# ST_LINK_V2-1.net
KiCad netlist of a schematic drawn in Altium Designer
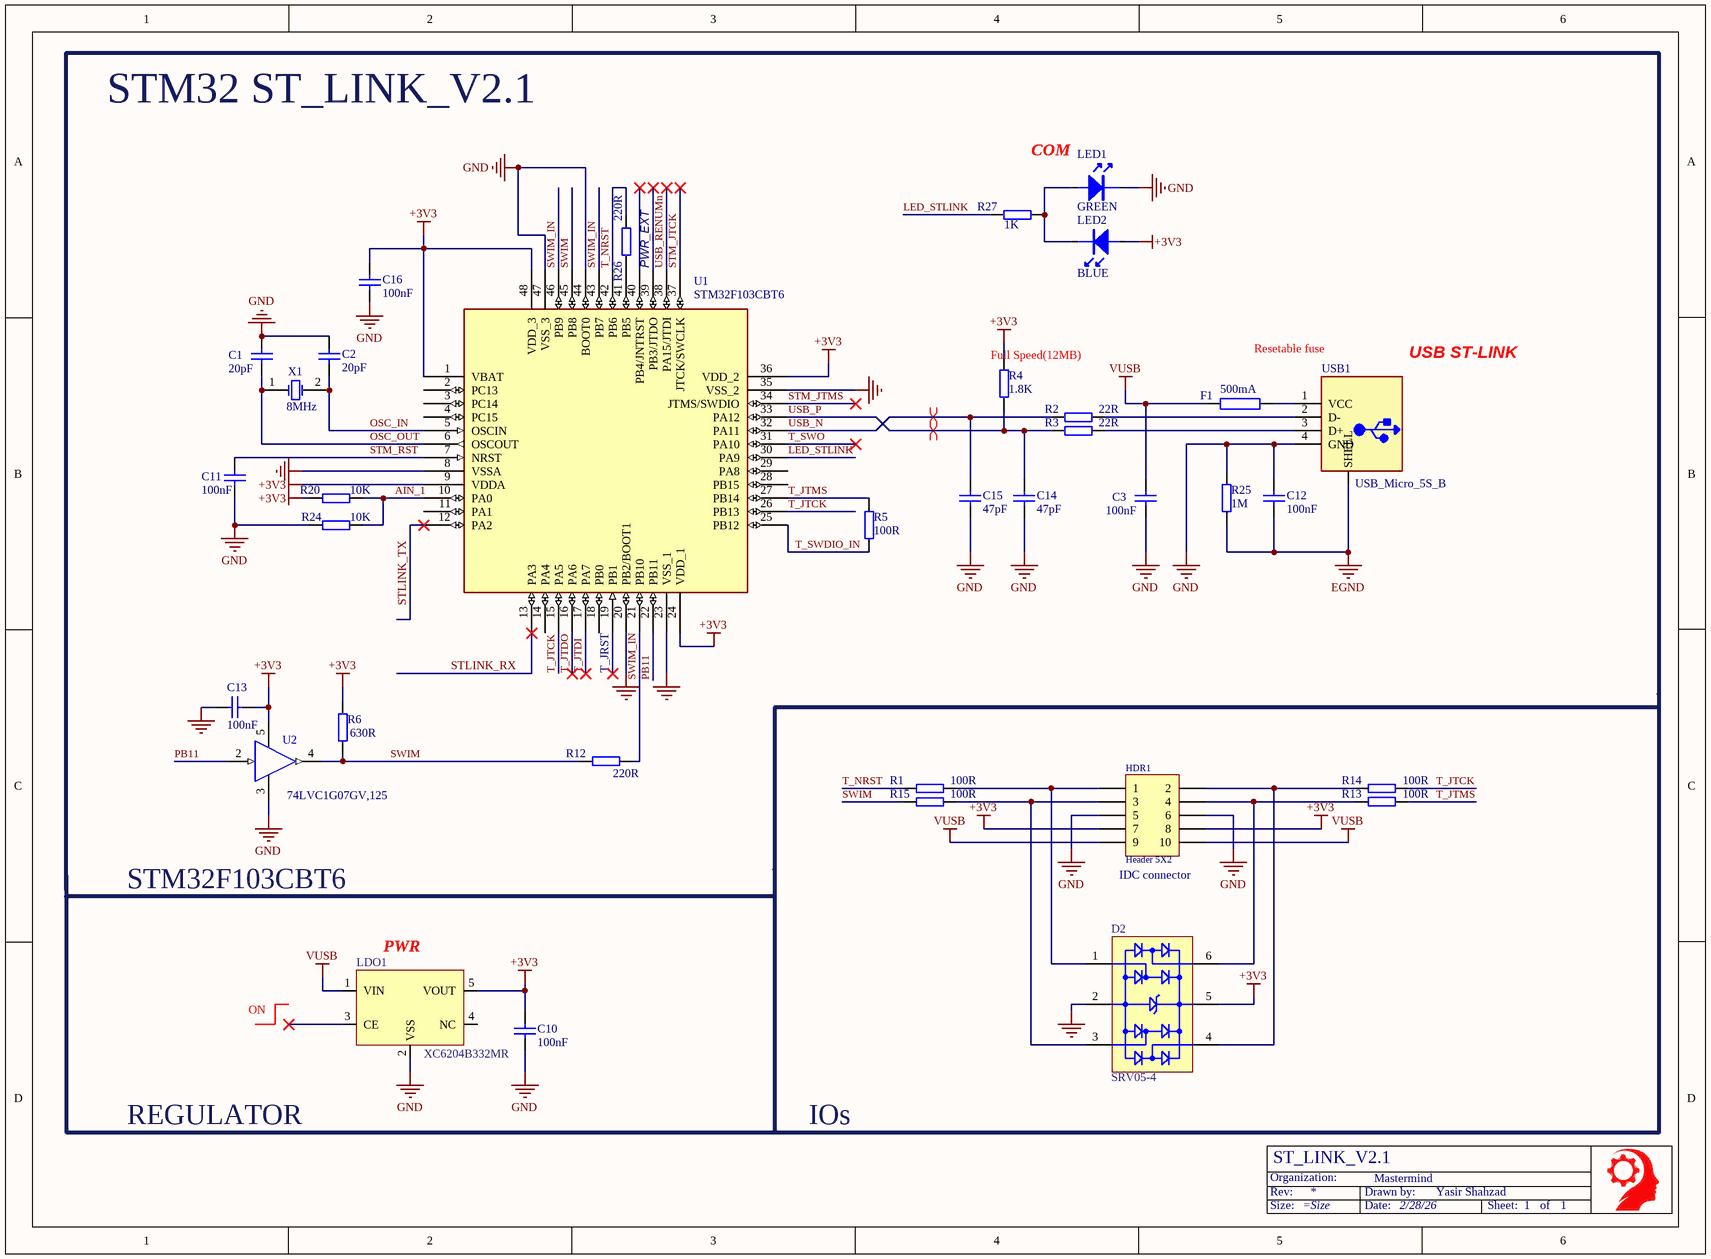
[diagram p0: ST_LINK_V2-1.SchDoc]

(export (version "E")
  (design (tool "Eeschema 10.0.6"))
  (components
    (comp (ref "*")
      (value "TitleBlock")
      (description "Title Block for Schematic Sheets")
      (libsource (lib "Mastermind Devices") (part "TitleBlock"))
    )
    (comp (ref "C1")
      (value "20pF")
      (footprint "C0603-NO")
      (description "CAP CER ?nF ?V X7R 0603")
      (libsource (lib "Mastermind Devices") (part "Cap_0603"))
    )
    (comp (ref "C2")
      (value "20pF")
      (footprint "C0603-NO")
      (description "CAP CER ?nF ?V X7R 0603")
      (libsource (lib "Mastermind Devices") (part "Cap_0603"))
    )
    (comp (ref "C3")
      (value "100nF")
      (footprint "C0603-NO")
      (description "CAP CER ?nF ?V X7R 0603")
      (libsource (lib "Mastermind Devices") (part "Cap_0603"))
    )
    (comp (ref "C10")
      (value "100nF")
      (footprint "C0603-NO")
      (description "CAP CER ?nF ?V X7R 0603")
      (libsource (lib "Mastermind Devices") (part "Cap_0603"))
    )
    (comp (ref "C11")
      (value "100nF")
      (footprint "C0603-NO")
      (description "CAP CER ?nF ?V X7R 0603")
      (libsource (lib "Mastermind Devices") (part "Cap_0603"))
    )
    (comp (ref "C12")
      (value "100nF")
      (footprint "C0603-NO")
      (description "CAP CER ?nF ?V X7R 0603")
      (libsource (lib "Mastermind Devices") (part "Cap_0603"))
    )
    (comp (ref "C13")
      (value "100nF")
      (footprint "C0603-NO")
      (description "CAP CER ?nF ?V X7R 0603")
      (libsource (lib "Mastermind Devices") (part "Cap_0603"))
    )
    (comp (ref "C14")
      (value "47pF")
      (footprint "C0603-NO")
      (description "CAP CER ?nF ?V X7R 0603")
      (libsource (lib "Mastermind Devices") (part "Cap_0603"))
    )
    (comp (ref "C15")
      (value "47pF")
      (footprint "C0603-NO")
      (description "CAP CER ?nF ?V X7R 0603")
      (libsource (lib "Mastermind Devices") (part "Cap_0603"))
    )
    (comp (ref "C16")
      (value "100nF")
      (footprint "C0603-NO")
      (description "CAP CER ?nF ?V X7R 0603")
      (libsource (lib "Mastermind Devices") (part "Cap_0603"))
    )
    (comp (ref "D2")
      (value "SRV05-4")
      (footprint "SOT23-6")
      (fields (field (name "MANUFACTURER") "MSKSEMI(美森科)"))
      (libsource (lib "ST_LINK_V2-1") (part "SRV05-4"))
    )
    (comp (ref "F1")
      (value "500mA")
      (footprint "F1206")
      (description "Resetable fuse")
      (fields (field (name "Comment") "Resistor_FUSE"))
      (libsource (lib "adafruit") (part "Resistor_FUSE"))
    )
    (comp (ref "HDR1")
      (value "Header 5X2")
      (footprint "IDC10_2SIDED")
      (description "Header, 5-Pin, Dual row")
      (libsource (lib "adafruit") (part "Header 5X2"))
    )
    (comp (ref "LDO1")
      (value "XC6204B332MR")
      (footprint "SOT23-5L")
      (fields (field (name "MANUFACTURER") "TOREX(特瑞仕)"))
      (libsource (lib "adafruit") (part "XC6204B332MR"))
    )
    (comp (ref "LED1")
      (value "GREEN")
      (footprint "CHIPLED_0603 - NO")
      (description "SMD lamp beads")
      (libsource (lib "Mastermind Devices") (part "LEDCHIP-LED0603"))
    )
    (comp (ref "LED2")
      (value "BLUE")
      (footprint "CHIPLED_0603 - NO")
      (description "SMD lamp beads")
      (libsource (lib "Mastermind Devices") (part "LEDCHIP-LED0603"))
    )
    (comp (ref "R1")
      (value "100R")
      (footprint "R0603-NO")
      (description "RES SMD ?K OHM 1% 1/10W 0603")
      (libsource (lib "Mastermind Devices") (part "Res_0603"))
    )
    (comp (ref "R2")
      (value "22R")
      (footprint "R0603-NO")
      (description "RES SMD ?K OHM 1% 1/10W 0603")
      (libsource (lib "") (part "Res_0603_3"))
    )
    (comp (ref "R3")
      (value "22R")
      (footprint "R0603-NO")
      (description "RES SMD ?K OHM 1% 1/10W 0603")
      (libsource (lib "") (part "Res_0603_3"))
    )
    (comp (ref "R4")
      (value "1.8K")
      (footprint "R0603-NO")
      (description "RES SMD ?K OHM 1% 1/10W 0603")
      (libsource (lib "Mastermind Devices") (part "Res_0603"))
    )
    (comp (ref "R5")
      (value "100R")
      (footprint "R0603-NO")
      (description "RES SMD ?K OHM 1% 1/10W 0603")
      (libsource (lib "") (part "Res_0603_2"))
    )
    (comp (ref "R6")
      (value "630R")
      (footprint "R0603-NO")
      (description "RES SMD ?K OHM 1% 1/10W 0603")
      (libsource (lib "") (part "Res_0603_1"))
    )
    (comp (ref "R12")
      (value "220R")
      (footprint "R0603-NO")
      (description "RES SMD ?K OHM 1% 1/10W 0603")
      (libsource (lib "") (part "Res_0603_2"))
    )
    (comp (ref "R13")
      (value "100R")
      (footprint "R0603-NO")
      (description "RES SMD ?K OHM 1% 1/10W 0603")
      (libsource (lib "") (part "Res_0603_1"))
    )
    (comp (ref "R14")
      (value "100R")
      (footprint "R0603-NO")
      (description "RES SMD ?K OHM 1% 1/10W 0603")
      (libsource (lib "") (part "Res_0603_3"))
    )
    (comp (ref "R15")
      (value "100R")
      (footprint "R0603-NO")
      (description "RES SMD ?K OHM 1% 1/10W 0603")
      (libsource (lib "") (part "Res_0603_3"))
    )
    (comp (ref "R20")
      (value "10K")
      (footprint "R0603-NO")
      (description "RES SMD ?K OHM 1% 1/10W 0603")
      (libsource (lib "") (part "Res_0603_2"))
    )
    (comp (ref "R24")
      (value "10K")
      (footprint "R0603-NO")
      (description "RES SMD ?K OHM 1% 1/10W 0603")
      (libsource (lib "Mastermind Devices") (part "Res_0603"))
    )
    (comp (ref "R25")
      (value "1M")
      (footprint "R0603-NO")
      (description "RES SMD ?K OHM 1% 1/10W 0603")
      (libsource (lib "") (part "Res_0603_1"))
    )
    (comp (ref "R26")
      (value "220R")
      (footprint "R0603-NO")
      (description "RES SMD ?K OHM 1% 1/10W 0603")
      (libsource (lib "") (part "Res_0603_1"))
    )
    (comp (ref "R27")
      (value "1K")
      (footprint "R0603-NO")
      (description "RES SMD ?K OHM 1% 1/10W 0603")
      (libsource (lib "Mastermind Devices") (part "Res_0603"))
    )
    (comp (ref "U1")
      (value "STM32F103CBT6")
      (footprint "QFP48 7X7")
      (description "Medium-density performance line ARM-based 32-bit MCU with 64KB Flash")
      (libsource (lib "ST_LINK_V2-1") (part "STM32F103CBT6"))
    )
    (comp (ref "U2")
      (value "74LVC1G07GV,125")
      (footprint "SOT23-5L")
      (fields (field (name "MANUFACTURER") "Nexperia(安世)"))
      (libsource (lib "adafruit") (part "74LVC1G07GV,125"))
    )
    (comp (ref "USB1")
      (value "USB ConnectorsUSBMINIB - Surface Mount Female Mini-B USB Connector 4UConnector: 06564   By microbuilder.euThru-hole RA Female Mini-B USB Connector 4UConnector: 18732   By ladyada.net")
      (footprint "USB-A-SMT_48037-0001")
      (fields (field (name "NAME") "USB_Micro_5S_B"))
      (libsource (lib "ST_LINK_V2-1") (part "USB-MALE"))
    )
    (comp (ref "X1")
      (value "8MHz")
      (footprint "XTAL1")
      (description "Crystal Oscillator")
      (fields (field (name "PUBLISHER") "Altium Limited"))
      (libsource (lib "MB963_1") (part "XTAL"))
    )
  )
  (nets
    (net (code "1") (name "+3V3") (class "Default")
      (node (ref "C10") (pin "2") (pinfunction "2_2") (pintype "passive"))
      (node (ref "C13") (pin "2") (pinfunction "2_2") (pintype "passive"))
      (node (ref "C16") (pin "2") (pinfunction "2_2") (pintype "passive"))
      (node (ref "D2") (pin "5") (pinfunction "VBUS_5") (pintype "passive"))
      (node (ref "HDR1") (pin "7") (pinfunction "7_7") (pintype "passive"))
      (node (ref "HDR1") (pin "8") (pinfunction "8_8") (pintype "passive"))
      (node (ref "LDO1") (pin "5") (pinfunction "VOUT_5") (pintype "passive"))
      (node (ref "LED2") (pin "A") (pinfunction "A_A") (pintype "passive"))
      (node (ref "R20") (pin "1") (pinfunction "1_1") (pintype "passive"))
      (node (ref "R4") (pin "1") (pinfunction "1_1") (pintype "passive"))
      (node (ref "R6") (pin "1") (pinfunction "1_1") (pintype "passive"))
      (node (ref "U1") (pin "1") (pinfunction "VBAT_1") (pintype "power_in"))
      (node (ref "U1") (pin "24") (pinfunction "VDD_1_24") (pintype "power_in"))
      (node (ref "U1") (pin "36") (pinfunction "VDD_2_36") (pintype "power_in"))
      (node (ref "U1") (pin "48") (pinfunction "VDD_3_48") (pintype "power_in"))
      (node (ref "U1") (pin "9") (pinfunction "VDDA_9") (pintype "power_in"))
      (node (ref "U2") (pin "5") (pinfunction "VCC_5") (pintype "passive"))
    )
    (net (code "2") (name "/AIN_1") (class "Default")
      (node (ref "R20") (pin "2") (pinfunction "2_2") (pintype "passive"))
      (node (ref "R24") (pin "1") (pinfunction "1_1") (pintype "passive"))
      (node (ref "U1") (pin "10") (pinfunction "PA0_10") (pintype "bidirectional"))
    )
    (net (code "3") (name "/LED_STLINK") (class "Default")
      (node (ref "R27") (pin "2") (pinfunction "2_2") (pintype "passive"))
      (node (ref "U1") (pin "30") (pinfunction "PA9_30") (pintype "bidirectional"))
    )
    (net (code "4") (name "/OSC_IN") (class "Default")
      (node (ref "C2") (pin "1") (pinfunction "1_1") (pintype "passive"))
      (node (ref "U1") (pin "5") (pinfunction "OSCIN_5") (pintype "input"))
      (node (ref "X1") (pin "2") (pinfunction "OSC2_2") (pintype "passive"))
    )
    (net (code "5") (name "/OSC_OUT") (class "Default")
      (node (ref "C1") (pin "1") (pinfunction "1_1") (pintype "passive"))
      (node (ref "U1") (pin "6") (pinfunction "OSCOUT_6") (pintype "output"))
      (node (ref "X1") (pin "1") (pinfunction "OSC1_1") (pintype "passive"))
    )
    (net (code "6") (name "/PB11") (class "Default")
      (node (ref "U1") (pin "22") (pinfunction "PB11_22") (pintype "bidirectional"))
      (node (ref "U2") (pin "2") (pinfunction "A_2") (pintype "input"))
    )
    (net (code "7") (name "/STLINK_RX") (class "Default")
      (node (ref "U1") (pin "13") (pinfunction "PA3_13") (pintype "bidirectional+no_connect"))
    )
    (net (code "8") (name "/STLINK_TX") (class "Default")
      (node (ref "U1") (pin "12") (pinfunction "PA2_12") (pintype "bidirectional+no_connect"))
    )
    (net (code "9") (name "/STM_JTCK") (class "Default")
      (node (ref "U1") (pin "37") (pinfunction "JTCK/SWCLK_37") (pintype "bidirectional+no_connect"))
    )
    (net (code "10") (name "/STM_JTMS") (class "Default")
      (node (ref "U1") (pin "34") (pinfunction "JTMS/SWDIO_34") (pintype "bidirectional+no_connect"))
    )
    (net (code "11") (name "/STM_RST") (class "Default")
      (node (ref "C11") (pin "2") (pinfunction "2_2") (pintype "passive"))
      (node (ref "U1") (pin "7") (pinfunction "NRST_7") (pintype "input"))
    )
    (net (code "12") (name "/SWIM") (class "Default")
      (node (ref "R12") (pin "1") (pinfunction "1_1") (pintype "passive"))
      (node (ref "R15") (pin "1") (pinfunction "1_1") (pintype "passive"))
      (node (ref "R6") (pin "2") (pinfunction "2_2") (pintype "passive"))
      (node (ref "U1") (pin "45") (pinfunction "PB8_45") (pintype "bidirectional"))
      (node (ref "U2") (pin "4") (pinfunction "Y_4") (pintype "output"))
    )
    (net (code "13") (name "/SWIM_IN") (class "Default")
      (node (ref "R12") (pin "2") (pinfunction "2_2") (pintype "passive"))
      (node (ref "U1") (pin "21") (pinfunction "PB10_21") (pintype "bidirectional"))
      (node (ref "U1") (pin "43") (pinfunction "PB7_43") (pintype "bidirectional"))
      (node (ref "U1") (pin "46") (pinfunction "PB9_46") (pintype "bidirectional"))
    )
    (net (code "14") (name "/T_JTCK") (class "Default")
      (node (ref "R14") (pin "2") (pinfunction "2_2") (pintype "passive"))
      (node (ref "U1") (pin "15") (pinfunction "PA5_15") (pintype "bidirectional"))
      (node (ref "U1") (pin "26") (pinfunction "PB13_26") (pintype "bidirectional"))
    )
    (net (code "15") (name "/T_JTDI") (class "Default")
      (node (ref "U1") (pin "17") (pinfunction "PA7_17") (pintype "bidirectional+no_connect"))
    )
    (net (code "16") (name "/T_JTDO") (class "Default")
      (node (ref "U1") (pin "16") (pinfunction "PA6_16") (pintype "bidirectional+no_connect"))
    )
    (net (code "17") (name "/T_JTMS") (class "Default")
      (node (ref "R13") (pin "1") (pinfunction "1_1") (pintype "passive"))
      (node (ref "R5") (pin "2") (pinfunction "2_2") (pintype "passive"))
      (node (ref "U1") (pin "27") (pinfunction "PB14_27") (pintype "bidirectional"))
    )
    (net (code "18") (name "/T_NRST") (class "Default")
      (node (ref "R1") (pin "2") (pinfunction "2_2") (pintype "passive"))
      (node (ref "R26") (pin "1") (pinfunction "1_1") (pintype "passive"))
      (node (ref "U1") (pin "42") (pinfunction "PB6_42") (pintype "bidirectional"))
    )
    (net (code "19") (name "/T_SWDIO_IN") (class "Default")
      (node (ref "R5") (pin "1") (pinfunction "1_1") (pintype "passive"))
      (node (ref "U1") (pin "25") (pinfunction "PB12_25") (pintype "bidirectional"))
    )
    (net (code "20") (name "/T_SWO") (class "Default")
      (node (ref "U1") (pin "31") (pinfunction "PA10_31") (pintype "bidirectional+no_connect"))
    )
    (net (code "21") (name "/USB_N") (class "Default")
      (node (ref "C15") (pin "2") (pinfunction "2_2") (pintype "passive"))
      (node (ref "R2") (pin "1") (pinfunction "1_1") (pintype "passive"))
      (node (ref "U1") (pin "32") (pinfunction "PA11_32") (pintype "bidirectional"))
    )
    (net (code "22") (name "/USB_P") (class "Default")
      (node (ref "C14") (pin "2") (pinfunction "2_2") (pintype "passive"))
      (node (ref "R3") (pin "1") (pinfunction "1_1") (pintype "passive"))
      (node (ref "R4") (pin "2") (pinfunction "2_2") (pintype "passive"))
      (node (ref "U1") (pin "33") (pinfunction "PA12_33") (pintype "bidirectional"))
    )
    (net (code "23") (name "/USB_RENUMn") (class "Default")
      (node (ref "U1") (pin "38") (pinfunction "PA15/JTDI_38") (pintype "bidirectional+no_connect"))
    )
    (net (code "24") (name "EGND") (class "Default")
      (node (ref "C12") (pin "2") (pinfunction "2_2") (pintype "passive"))
      (node (ref "R25") (pin "2") (pinfunction "2_2") (pintype "passive"))
      (node (ref "USB1") (pin "5") (pinfunction "SHELL_5") (pintype "power_in"))
    )
    (net (code "25") (name "GND") (class "Default")
      (node (ref "C1") (pin "2") (pinfunction "2_2") (pintype "passive"))
      (node (ref "C10") (pin "1") (pinfunction "1_1") (pintype "passive"))
      (node (ref "C11") (pin "1") (pinfunction "1_1") (pintype "passive"))
      (node (ref "C12") (pin "1") (pinfunction "1_1") (pintype "passive"))
      (node (ref "C13") (pin "1") (pinfunction "1_1") (pintype "passive"))
      (node (ref "C14") (pin "1") (pinfunction "1_1") (pintype "passive"))
      (node (ref "C15") (pin "1") (pinfunction "1_1") (pintype "passive"))
      (node (ref "C16") (pin "1") (pinfunction "1_1") (pintype "passive"))
      (node (ref "C2") (pin "2") (pinfunction "2_2") (pintype "passive"))
      (node (ref "C3") (pin "1") (pinfunction "1_1") (pintype "passive"))
      (node (ref "D2") (pin "2") (pinfunction "GND_2") (pintype "passive"))
      (node (ref "HDR1") (pin "5") (pinfunction "5_5") (pintype "passive"))
      (node (ref "HDR1") (pin "6") (pinfunction "6_6") (pintype "passive"))
      (node (ref "LDO1") (pin "2") (pinfunction "VSS_2") (pintype "passive"))
      (node (ref "LED1") (pin "C") (pinfunction "K_C") (pintype "passive"))
      (node (ref "R24") (pin "2") (pinfunction "2_2") (pintype "passive"))
      (node (ref "R25") (pin "1") (pinfunction "1_1") (pintype "passive"))
      (node (ref "U1") (pin "20") (pinfunction "PB2/BOOT1_20") (pintype "bidirectional"))
      (node (ref "U1") (pin "23") (pinfunction "VSS_1_23") (pintype "power_in"))
      (node (ref "U1") (pin "35") (pinfunction "VSS_2_35") (pintype "power_in"))
      (node (ref "U1") (pin "44") (pinfunction "BOOT0_44") (pintype "bidirectional"))
      (node (ref "U1") (pin "47") (pinfunction "VSS_3_47") (pintype "power_in"))
      (node (ref "U1") (pin "8") (pinfunction "VSSA_8") (pintype "power_in"))
      (node (ref "U2") (pin "3") (pinfunction "GND_3") (pintype "passive"))
      (node (ref "USB1") (pin "4") (pinfunction "GND_4") (pintype "passive"))
    )
    (net (code "26") (name "Net-(D2-I{slash}O_1)") (class "Default")
      (node (ref "D2") (pin "1") (pinfunction "I/O_1_1") (pintype "passive"))
      (node (ref "HDR1") (pin "1") (pinfunction "1_1") (pintype "passive"))
      (node (ref "R1") (pin "1") (pinfunction "1_1") (pintype "passive"))
    )
    (net (code "27") (name "Net-(D2-I{slash}O_2)") (class "Default")
      (node (ref "D2") (pin "3") (pinfunction "I/O_2_3") (pintype "passive"))
      (node (ref "HDR1") (pin "3") (pinfunction "3_3") (pintype "passive"))
      (node (ref "R15") (pin "2") (pinfunction "2_2") (pintype "passive"))
    )
    (net (code "28") (name "Net-(D2-I{slash}O_3)") (class "Default")
      (node (ref "D2") (pin "4") (pinfunction "I/O_3_4") (pintype "passive"))
      (node (ref "HDR1") (pin "2") (pinfunction "2_2") (pintype "passive"))
      (node (ref "R14") (pin "1") (pinfunction "1_1") (pintype "passive"))
    )
    (net (code "29") (name "Net-(D2-I{slash}O_4)") (class "Default")
      (node (ref "D2") (pin "6") (pinfunction "I/O_4_6") (pintype "passive"))
      (node (ref "HDR1") (pin "4") (pinfunction "4_4") (pintype "passive"))
      (node (ref "R13") (pin "2") (pinfunction "2_2") (pintype "passive"))
    )
    (net (code "30") (name "Net-(LED2-K)") (class "Default")
      (node (ref "LED1") (pin "A") (pinfunction "A_A") (pintype "passive"))
      (node (ref "LED2") (pin "C") (pinfunction "K_C") (pintype "passive"))
      (node (ref "R27") (pin "1") (pinfunction "1_1") (pintype "passive"))
    )
    (net (code "31") (name "Net-(U1-PB5)") (class "Default")
      (node (ref "R26") (pin "2") (pinfunction "2_2") (pintype "passive"))
      (node (ref "U1") (pin "41") (pinfunction "PB5_41") (pintype "bidirectional"))
    )
    (net (code "32") (name "Net-(USB1-D+)") (class "Default")
      (node (ref "R3") (pin "2") (pinfunction "2_2") (pintype "passive"))
      (node (ref "USB1") (pin "3") (pinfunction "D+_3") (pintype "passive"))
    )
    (net (code "33") (name "Net-(USB1-D-)") (class "Default")
      (node (ref "R2") (pin "2") (pinfunction "2_2") (pintype "passive"))
      (node (ref "USB1") (pin "2") (pinfunction "D-_2") (pintype "passive"))
    )
    (net (code "34") (name "Net-(USB1-VCC)") (class "Default")
      (node (ref "F1") (pin "1") (pinfunction "1_1") (pintype "passive"))
      (node (ref "USB1") (pin "1") (pinfunction "VCC_1") (pintype "power_in"))
    )
    (net (code "35") (name "VUSB") (class "Default")
      (node (ref "C3") (pin "2") (pinfunction "2_2") (pintype "passive"))
      (node (ref "F1") (pin "2") (pinfunction "2_2") (pintype "passive"))
      (node (ref "HDR1") (pin "10") (pinfunction "10_10") (pintype "passive"))
      (node (ref "HDR1") (pin "9") (pinfunction "9_9") (pintype "passive"))
      (node (ref "LDO1") (pin "1") (pinfunction "VIN_1") (pintype "passive"))
    )
    (net (code "36") (name "unconnected-(LDO1-CE-Pad3)") (class "Default")
      (node (ref "LDO1") (pin "3") (pinfunction "CE_3") (pintype "passive+no_connect"))
    )
    (net (code "37") (name "unconnected-(LDO1-NC-Pad4)") (class "Default")
      (node (ref "LDO1") (pin "4") (pinfunction "NC_4") (pintype "passive"))
    )
    (net (code "38") (name "unconnected-(U1-PA1-Pad11)") (class "Default")
      (node (ref "U1") (pin "11") (pinfunction "PA1_11") (pintype "bidirectional"))
    )
    (net (code "39") (name "unconnected-(U1-PA4-Pad14)") (class "Default")
      (node (ref "U1") (pin "14") (pinfunction "PA4_14") (pintype "bidirectional"))
    )
    (net (code "40") (name "unconnected-(U1-PA8-Pad29)") (class "Default")
      (node (ref "U1") (pin "29") (pinfunction "PA8_29") (pintype "bidirectional"))
    )
    (net (code "41") (name "unconnected-(U1-PB0-Pad18)") (class "Default")
      (node (ref "U1") (pin "18") (pinfunction "PB0_18") (pintype "bidirectional"))
    )
    (net (code "42") (name "unconnected-(U1-PB1-Pad19)") (class "Default")
      (node (ref "U1") (pin "19") (pinfunction "PB1_19") (pintype "input+no_connect"))
    )
    (net (code "43") (name "unconnected-(U1-PB3{slash}JTDO-Pad39)") (class "Default")
      (node (ref "U1") (pin "39") (pinfunction "PB3/JTDO_39") (pintype "bidirectional+no_connect"))
    )
    (net (code "44") (name "unconnected-(U1-PB4{slash}JNTRST-Pad40)") (class "Default")
      (node (ref "U1") (pin "40") (pinfunction "PB4/JNTRST_40") (pintype "bidirectional+no_connect"))
    )
    (net (code "45") (name "unconnected-(U1-PB15-Pad28)") (class "Default")
      (node (ref "U1") (pin "28") (pinfunction "PB15_28") (pintype "bidirectional"))
    )
    (net (code "46") (name "unconnected-(U1-PC13-Pad2)") (class "Default")
      (node (ref "U1") (pin "2") (pinfunction "PC13_2") (pintype "bidirectional"))
    )
    (net (code "47") (name "unconnected-(U1-PC14-Pad3)") (class "Default")
      (node (ref "U1") (pin "3") (pinfunction "PC14_3") (pintype "bidirectional"))
    )
    (net (code "48") (name "unconnected-(U1-PC15-Pad4)") (class "Default")
      (node (ref "U1") (pin "4") (pinfunction "PC15_4") (pintype "bidirectional"))
    )
  )
)
